# AD5293-adapter.net
KiCad netlist of a schematic drawn in EAGLE
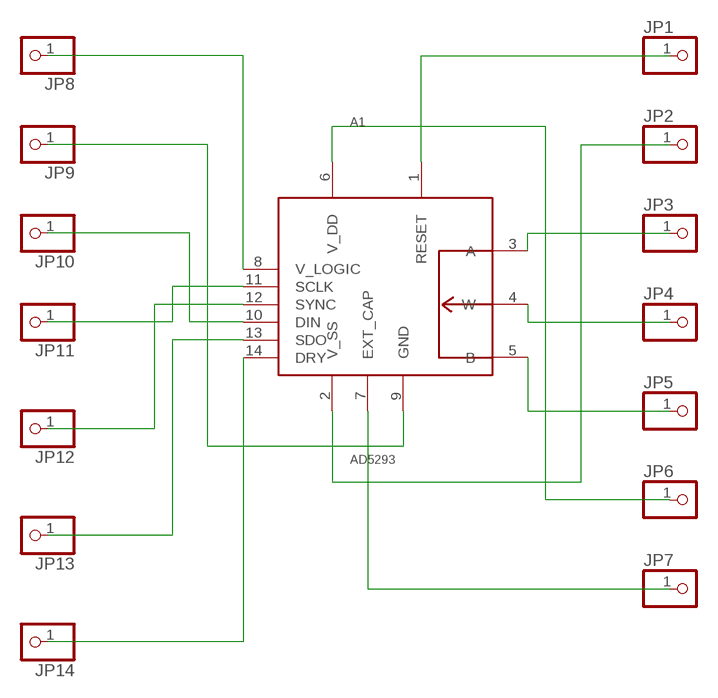
[diagram p0: schematic, sheet 1]

(export (version "E")
  (design (tool "Eeschema 10.0.6"))
  (components
    (comp (ref "A1")
      (value "AD5293")
      (footprint "eagle-import:AD5293")
      (libsource (lib "eagle-import") (part "AD5293"))
    )
    (comp (ref "JP1")
      (value "PINHD-1X1-SQUARE")
      (footprint "eagle-import:1X01-SQUARE")
      (libsource (lib "eagle-import") (part "PINHD-1X1-SQUARE"))
    )
    (comp (ref "JP2")
      (value "PINHD-1X1")
      (footprint "eagle-import:1X01")
      (libsource (lib "eagle-import") (part "PINHD-1X1"))
    )
    (comp (ref "JP3")
      (value "PINHD-1X1")
      (footprint "eagle-import:1X01")
      (libsource (lib "eagle-import") (part "PINHD-1X1"))
    )
    (comp (ref "JP4")
      (value "PINHD-1X1")
      (footprint "eagle-import:1X01")
      (libsource (lib "eagle-import") (part "PINHD-1X1"))
    )
    (comp (ref "JP5")
      (value "PINHD-1X1")
      (footprint "eagle-import:1X01")
      (libsource (lib "eagle-import") (part "PINHD-1X1"))
    )
    (comp (ref "JP6")
      (value "PINHD-1X1")
      (footprint "eagle-import:1X01")
      (libsource (lib "eagle-import") (part "PINHD-1X1"))
    )
    (comp (ref "JP7")
      (value "PINHD-1X1")
      (footprint "eagle-import:1X01")
      (libsource (lib "eagle-import") (part "PINHD-1X1"))
    )
    (comp (ref "JP8")
      (value "PINHD-1X1")
      (footprint "eagle-import:1X01")
      (libsource (lib "eagle-import") (part "PINHD-1X1"))
    )
    (comp (ref "JP9")
      (value "PINHD-1X1")
      (footprint "eagle-import:1X01")
      (libsource (lib "eagle-import") (part "PINHD-1X1"))
    )
    (comp (ref "JP10")
      (value "PINHD-1X1")
      (footprint "eagle-import:1X01")
      (libsource (lib "eagle-import") (part "PINHD-1X1"))
    )
    (comp (ref "JP11")
      (value "PINHD-1X1")
      (footprint "eagle-import:1X01")
      (libsource (lib "eagle-import") (part "PINHD-1X1"))
    )
    (comp (ref "JP12")
      (value "PINHD-1X1")
      (footprint "eagle-import:1X01")
      (libsource (lib "eagle-import") (part "PINHD-1X1"))
    )
    (comp (ref "JP13")
      (value "PINHD-1X1")
      (footprint "eagle-import:1X01")
      (libsource (lib "eagle-import") (part "PINHD-1X1"))
    )
    (comp (ref "JP14")
      (value "PINHD-1X1")
      (footprint "eagle-import:1X01")
      (libsource (lib "eagle-import") (part "PINHD-1X1"))
    )
  )
  (nets
    (net (code "1") (name "Net-(A1-A)") (class "Default")
      (node (ref "A1") (pin "3") (pinfunction "A_3") (pintype "passive"))
      (node (ref "JP3") (pin "1") (pinfunction "1_1") (pintype "passive"))
    )
    (net (code "2") (name "Net-(A1-B)") (class "Default")
      (node (ref "A1") (pin "5") (pinfunction "B_5") (pintype "passive"))
      (node (ref "JP5") (pin "1") (pinfunction "1_1") (pintype "passive"))
    )
    (net (code "3") (name "Net-(A1-DIN)") (class "Default")
      (node (ref "A1") (pin "10") (pinfunction "DIN_10") (pintype "bidirectional"))
      (node (ref "JP10") (pin "1") (pinfunction "1_1") (pintype "passive"))
    )
    (net (code "4") (name "Net-(A1-DRY)") (class "Default")
      (node (ref "A1") (pin "14") (pinfunction "DRY_14") (pintype "bidirectional"))
      (node (ref "JP14") (pin "1") (pinfunction "1_1") (pintype "passive"))
    )
    (net (code "5") (name "Net-(A1-EXT_CAP)") (class "Default")
      (node (ref "A1") (pin "7") (pinfunction "EXT_CAP_7") (pintype "passive"))
      (node (ref "JP7") (pin "1") (pinfunction "1_1") (pintype "passive"))
    )
    (net (code "6") (name "Net-(A1-GND)") (class "Default")
      (node (ref "A1") (pin "9") (pinfunction "GND_9") (pintype "power_in"))
      (node (ref "JP9") (pin "1") (pinfunction "1_1") (pintype "passive"))
    )
    (net (code "7") (name "Net-(A1-RESET)") (class "Default")
      (node (ref "A1") (pin "1") (pinfunction "RESET_1") (pintype "bidirectional"))
      (node (ref "JP1") (pin "1") (pinfunction "1_1") (pintype "passive"))
    )
    (net (code "8") (name "Net-(A1-SCLK)") (class "Default")
      (node (ref "A1") (pin "11") (pinfunction "SCLK_11") (pintype "bidirectional"))
      (node (ref "JP11") (pin "1") (pinfunction "1_1") (pintype "passive"))
    )
    (net (code "9") (name "Net-(A1-SDO)") (class "Default")
      (node (ref "A1") (pin "13") (pinfunction "SDO_13") (pintype "bidirectional"))
      (node (ref "JP13") (pin "1") (pinfunction "1_1") (pintype "passive"))
    )
    (net (code "10") (name "Net-(A1-SYNC)") (class "Default")
      (node (ref "A1") (pin "12") (pinfunction "SYNC_12") (pintype "bidirectional"))
      (node (ref "JP12") (pin "1") (pinfunction "1_1") (pintype "passive"))
    )
    (net (code "11") (name "Net-(A1-V_DD)") (class "Default")
      (node (ref "A1") (pin "6") (pinfunction "V_DD_6") (pintype "power_in"))
      (node (ref "JP6") (pin "1") (pinfunction "1_1") (pintype "passive"))
    )
    (net (code "12") (name "Net-(A1-V_LOGIC)") (class "Default")
      (node (ref "A1") (pin "8") (pinfunction "V_LOGIC_8") (pintype "bidirectional"))
      (node (ref "JP8") (pin "1") (pinfunction "1_1") (pintype "passive"))
    )
    (net (code "13") (name "Net-(A1-V_SS)") (class "Default")
      (node (ref "A1") (pin "2") (pinfunction "V_SS_2") (pintype "power_in"))
      (node (ref "JP2") (pin "1") (pinfunction "1_1") (pintype "passive"))
    )
    (net (code "14") (name "Net-(A1-W)") (class "Default")
      (node (ref "A1") (pin "4") (pinfunction "W_4") (pintype "passive"))
      (node (ref "JP4") (pin "1") (pinfunction "1_1") (pintype "passive"))
    )
  )
)
